# Ref_2V5_LM4132AMF.net
KiCad netlist of a schematic drawn in Altium Designer
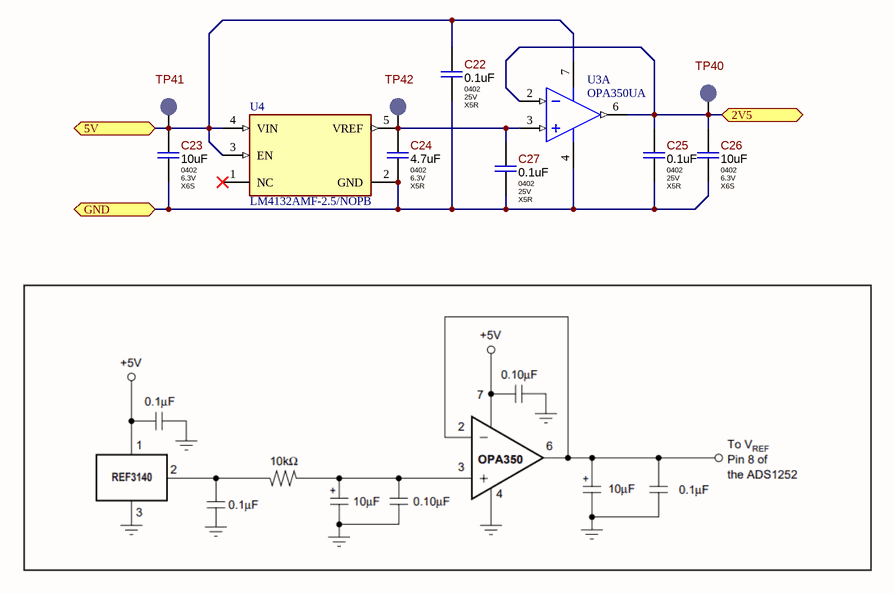
[diagram p0: Ref_2V5_LM4132AMF.SchDoc]

(export (version "E")
  (design (tool "Eeschema 10.0.6"))
  (components
    (comp (ref "C22")
      (value "0.1uF")
      (footprint "C_CERAMIC_0402_MED")
      (description "100nF 25V X5R ±10% 0402 Ceramic Capacitor RoHS")
      (fields
        (field (name "PACKAGE") "0402")
        (field (name "VOLTAGE") "25V")
        (field (name "DIELECTRIC TYPE") "X5R")
        (field (name "PART NUMBER") "CL05A104KA5NNNC")
        (field (name "MANUFACTURER") "Samsung Electro-Mechanics")
      )
      (libsource (lib "EL.CVCM.T01") (part "Capacitor-NonPolar"))
    )
    (comp (ref "C23")
      (value "10uF")
      (footprint "C_CERAMIC_0402_MED")
      (description "10uF 6.3V X6S ±20% 0402 Ceramic Capacitor RoHS")
      (fields
        (field (name "PACKAGE") "0402")
        (field (name "VOLTAGE") "6.3V")
        (field (name "DIELECTRIC TYPE") "X6S")
        (field (name "PART NUMBER") "GRM155C80J106ME11D")
        (field (name "MANUFACTURER") "Murata Electronics")
      )
      (libsource (lib "EL.CVCM.T01") (part "Capacitor-NonPolar"))
    )
    (comp (ref "C24")
      (value "4.7uF")
      (footprint "C_CERAMIC_0402_MED")
      (description "4.7uF 6.3V X5R ±20% 0402 Ceramic Capacitor RoHS")
      (fields
        (field (name "PACKAGE") "0402")
        (field (name "VOLTAGE") "6.3V")
        (field (name "DIELECTRIC TYPE") "X5R")
        (field (name "PART NUMBER") "GRM155R60J475ME47")
        (field (name "MANUFACTURER") "Murata Electronics")
      )
      (libsource (lib "EL.CVCM.T01") (part "Capacitor-NonPolar"))
    )
    (comp (ref "C25")
      (value "0.1uF")
      (footprint "C_CERAMIC_0402_MED")
      (description "100nF 25V X5R ±10% 0402 Ceramic Capacitor RoHS")
      (fields
        (field (name "PACKAGE") "0402")
        (field (name "VOLTAGE") "25V")
        (field (name "DIELECTRIC TYPE") "X5R")
        (field (name "PART NUMBER") "CL05A104KA5NNNC")
        (field (name "MANUFACTURER") "Samsung Electro-Mechanics")
      )
      (libsource (lib "EL.CVCM.T01") (part "Capacitor-NonPolar"))
    )
    (comp (ref "C26")
      (value "10uF")
      (footprint "C_CERAMIC_0402_MED")
      (description "10uF 6.3V X6S ±20% 0402 Ceramic Capacitor RoHS")
      (fields
        (field (name "PACKAGE") "0402")
        (field (name "VOLTAGE") "6.3V")
        (field (name "DIELECTRIC TYPE") "X6S")
        (field (name "PART NUMBER") "GRM155C80J106ME11D")
        (field (name "MANUFACTURER") "Murata Electronics")
      )
      (libsource (lib "EL.CVCM.T01") (part "Capacitor-NonPolar"))
    )
    (comp (ref "C27")
      (value "0.1uF")
      (footprint "C_CERAMIC_0402_MED")
      (description "100nF 25V X5R ±10% 0402 Ceramic Capacitor RoHS")
      (fields
        (field (name "PACKAGE") "0402")
        (field (name "VOLTAGE") "25V")
        (field (name "DIELECTRIC TYPE") "X5R")
        (field (name "PART NUMBER") "CL05A104KA5NNNC")
        (field (name "MANUFACTURER") "Samsung Electro-Mechanics")
      )
      (libsource (lib "EL.CVCM.T01") (part "Capacitor-NonPolar"))
    )
    (comp (ref "TP40")
      (value "LED_LINK")
      (footprint "TP_SMD_2mm")
      (description "Test Point SMD Pad 1.0mm/1.5mm/2mm")
      (fields (field (name "PART NUMBER") "TP-PAD-SMD"))
      (libsource (lib "EL.CVCM.T01") (part "Test-Point-SMD-1"))
    )
    (comp (ref "TP41")
      (value "LED_LINK")
      (footprint "TP_SMD_2mm")
      (description "Test Point SMD Pad 1.0mm/1.5mm/2mm")
      (fields (field (name "PART NUMBER") "TP-PAD-SMD"))
      (libsource (lib "EL.CVCM.T01") (part "Test-Point-SMD-1"))
    )
    (comp (ref "TP42")
      (value "LED_LINK")
      (footprint "TP_SMD_2mm")
      (description "Test Point SMD Pad 1.0mm/1.5mm/2mm")
      (fields (field (name "PART NUMBER") "TP-PAD-SMD"))
      (libsource (lib "EL.CVCM.T01") (part "Test-Point-SMD-1"))
    )
    (comp (ref "U3")
      (value "OPA350UA")
      (footprint "D0008A_M")
      (fields (field (name "MANUFACTURER") "Texas Instruments"))
      (libsource (lib "EL.CVCM.T01") (part "TI-OPA-8_1"))
    )
    (comp (ref "U4")
      (value "LM4132AMF-2.5/NOPB")
      (footprint "FP-DBV0005A-IPC_C")
      (description "IC VREF SERIES 0.05% SOT23-5")
      (fields (field (name "TOLERANCE") "0.05%"))
      (libsource (lib "EL.CVCM.T01") (part "83a8c20666b8818ecf60699c622df6d"))
    )
  )
  (nets
    (net (code "1") (name "/2V5") (class "Default")
      (node (ref "C25") (pin "1") (pinfunction "1_1") (pintype "passive"))
      (node (ref "C26") (pin "1") (pinfunction "1_1") (pintype "passive"))
      (node (ref "TP40") (pin "1") (pintype "passive"))
      (node (ref "U3") (pin "2") (pinfunction "IN-_2") (pintype "input"))
      (node (ref "U3") (pin "6") (pinfunction "OUT_6") (pintype "output"))
    )
    (net (code "2") (name "/5V") (class "Default")
      (node (ref "C22") (pin "1") (pinfunction "1_1") (pintype "passive"))
      (node (ref "C23") (pin "1") (pinfunction "1_1") (pintype "passive"))
      (node (ref "TP41") (pin "1") (pintype "passive"))
      (node (ref "U3") (pin "7") (pinfunction "V+_7") (pintype "power_in"))
      (node (ref "U4") (pin "3") (pinfunction "EN_3") (pintype "input"))
      (node (ref "U4") (pin "4") (pinfunction "VIN_4") (pintype "input"))
    )
    (net (code "3") (name "/GND") (class "Default")
      (node (ref "C22") (pin "2") (pinfunction "2_2") (pintype "passive"))
      (node (ref "C23") (pin "2") (pinfunction "2_2") (pintype "passive"))
      (node (ref "C24") (pin "2") (pinfunction "2_2") (pintype "passive"))
      (node (ref "C25") (pin "2") (pinfunction "2_2") (pintype "passive"))
      (node (ref "C26") (pin "2") (pinfunction "2_2") (pintype "passive"))
      (node (ref "C27") (pin "2") (pinfunction "2_2") (pintype "passive"))
      (node (ref "U3") (pin "4") (pinfunction "V-_4") (pintype "power_in"))
      (node (ref "U4") (pin "2") (pinfunction "GND_2") (pintype "power_in"))
    )
    (net (code "4") (name "Net-(U3A-IN+)") (class "Default")
      (node (ref "C24") (pin "1") (pinfunction "1_1") (pintype "passive"))
      (node (ref "C27") (pin "1") (pinfunction "1_1") (pintype "passive"))
      (node (ref "TP42") (pin "1") (pintype "passive"))
      (node (ref "U3") (pin "3") (pinfunction "IN+_3") (pintype "input"))
      (node (ref "U4") (pin "5") (pinfunction "VREF_5") (pintype "output"))
    )
    (net (code "5") (name "unconnected-(U4-NC-Pad1)") (class "Default")
      (node (ref "U4") (pin "1") (pinfunction "NC_1") (pintype "passive+no_connect"))
    )
  )
)
